# pcb01_control.net
KiCad netlist of a schematic drawn in EAGLE
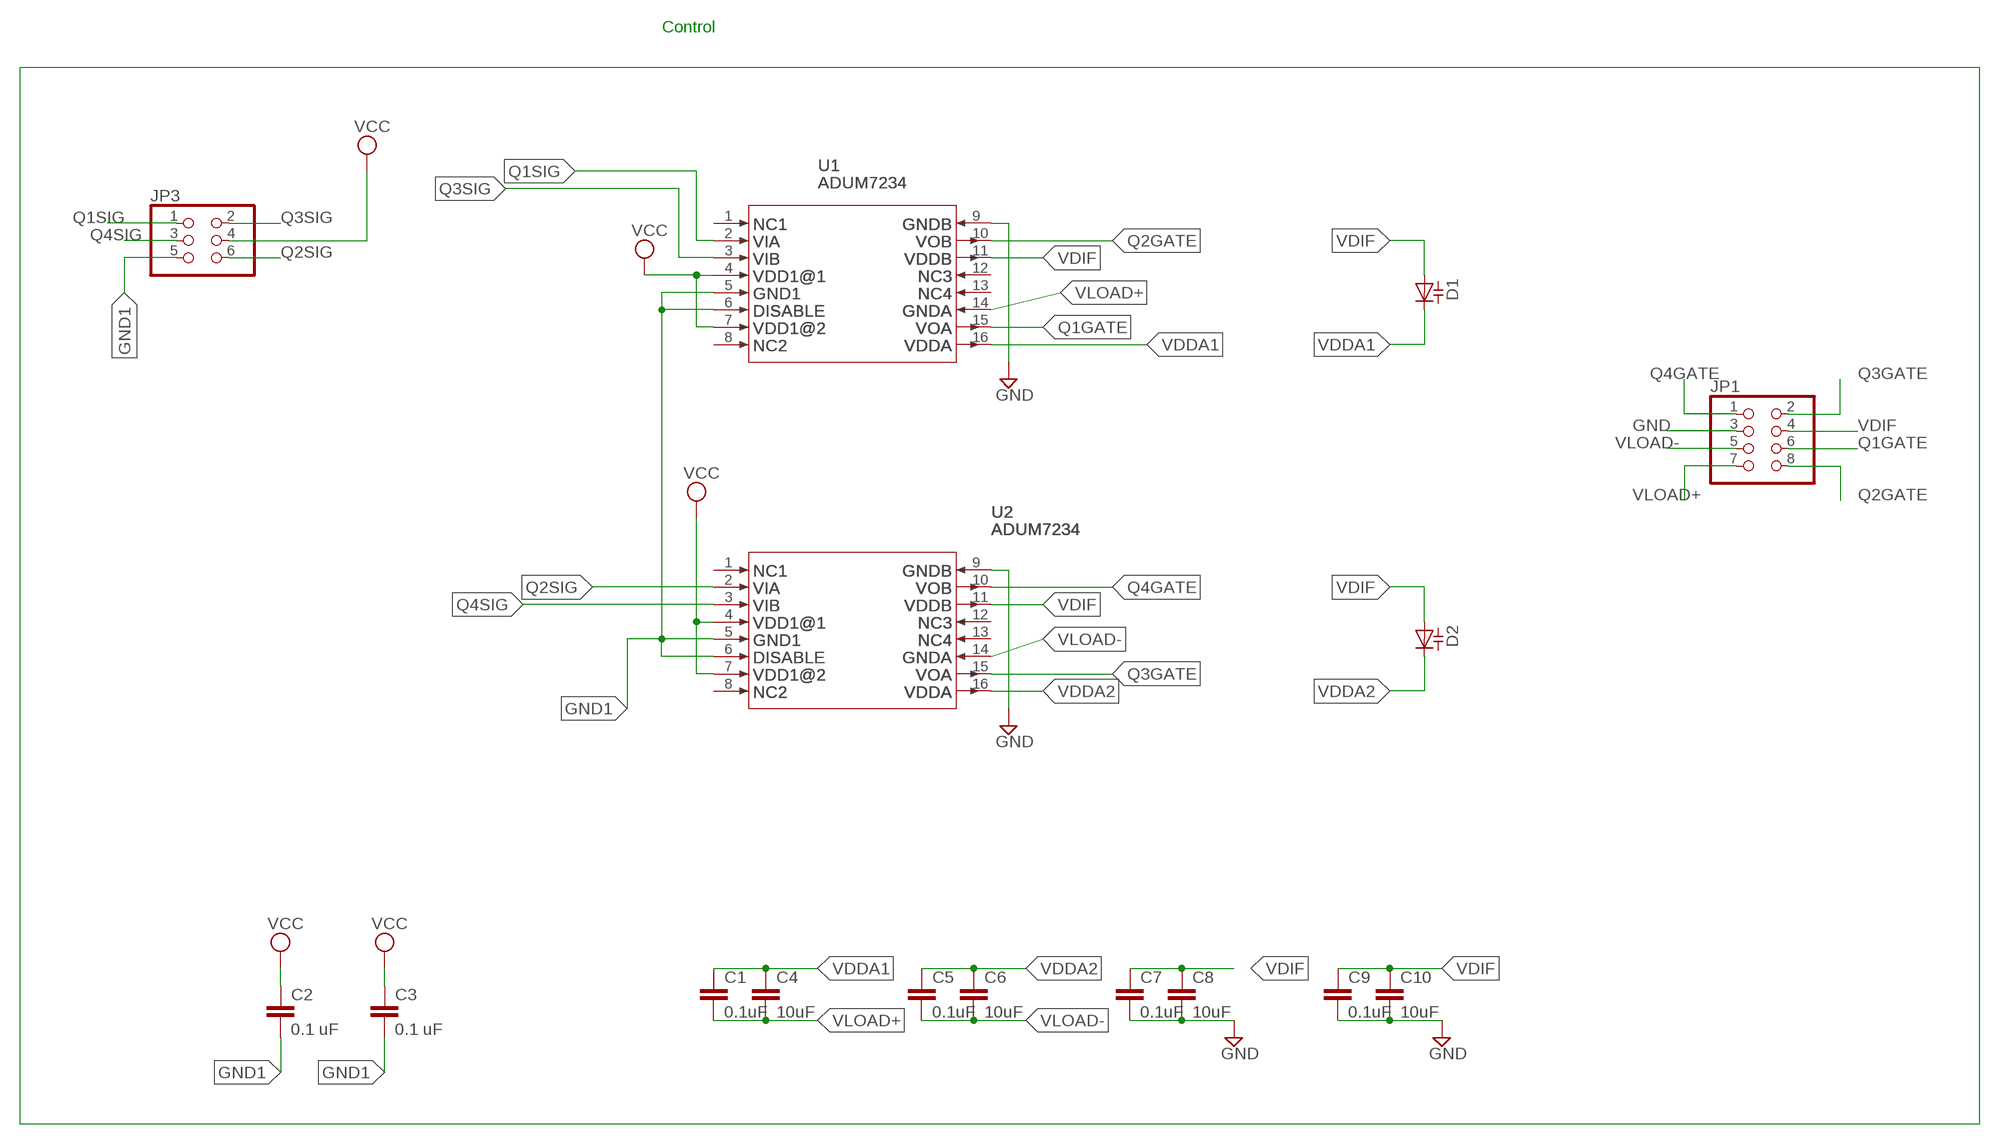
[diagram p0: schematic, sheet 1]

(export (version "E")
  (design (tool "Eeschema 10.0.6"))
  (components
    (comp (ref "C1")
      (value "0.1uF")
      (footprint "eagle-import:C0805")
      (libsource (lib "eagle-import") (part "resistor_C-EUC0805"))
    )
    (comp (ref "C2")
      (value "0.1 uF")
      (footprint "eagle-import:C0805")
      (libsource (lib "eagle-import") (part "C-EUC0805"))
    )
    (comp (ref "C3")
      (value "0.1 uF")
      (footprint "eagle-import:C0805")
      (libsource (lib "eagle-import") (part "C-EUC0805"))
    )
    (comp (ref "C4")
      (value "10uF")
      (footprint "eagle-import:C0805")
      (libsource (lib "eagle-import") (part "resistor_C-EUC0805"))
    )
    (comp (ref "C5")
      (value "0.1uF")
      (footprint "eagle-import:C0805")
      (libsource (lib "eagle-import") (part "resistor_C-EUC0805"))
    )
    (comp (ref "C6")
      (value "10uF")
      (footprint "eagle-import:C0805")
      (libsource (lib "eagle-import") (part "resistor_C-EUC0805"))
    )
    (comp (ref "C7")
      (value "0.1uF")
      (footprint "eagle-import:C0805")
      (libsource (lib "eagle-import") (part "resistor_C-EUC0805"))
    )
    (comp (ref "C8")
      (value "10uF")
      (footprint "eagle-import:C0805")
      (libsource (lib "eagle-import") (part "resistor_C-EUC0805"))
    )
    (comp (ref "C9")
      (value "0.1uF")
      (footprint "eagle-import:C0805")
      (libsource (lib "eagle-import") (part "resistor_C-EUC0805"))
    )
    (comp (ref "C10")
      (value "10uF")
      (footprint "eagle-import:C0805")
      (libsource (lib "eagle-import") (part "resistor_C-EUC0805"))
    )
    (comp (ref "D1")
      (value "DIODE_CAPACITANCE-SOD523")
      (footprint "eagle-import:SOD523")
      (libsource (lib "eagle-import") (part "DIODE_CAPACITANCE-SOD523"))
    )
    (comp (ref "D2")
      (value "DIODE_CAPACITANCE-SOD523")
      (footprint "eagle-import:SOD523")
      (libsource (lib "eagle-import") (part "DIODE_CAPACITANCE-SOD523"))
    )
    (comp (ref "JP1")
      (value "PINHD-2X4")
      (footprint "eagle-import:2X04")
      (libsource (lib "eagle-import") (part "PINHD-2X4"))
    )
    (comp (ref "JP3")
      (value "PINHD-2X3")
      (footprint "eagle-import:2X03")
      (libsource (lib "eagle-import") (part "PINHD-2X3"))
    )
    (comp (ref "U1")
      (value "ADUM7234")
      (footprint "eagle-import:16_SOIC")
      (libsource (lib "eagle-import") (part "ADUM7234"))
    )
    (comp (ref "U2")
      (value "ADUM7234")
      (footprint "eagle-import:16_SOIC")
      (libsource (lib "eagle-import") (part "ADUM7234"))
    )
  )
  (nets
    (net (code "1") (name "GND") (class "Default")
      (node (ref "C10") (pin "2") (pinfunction "2_2") (pintype "passive"))
      (node (ref "C7") (pin "2") (pinfunction "2_2") (pintype "passive"))
      (node (ref "C8") (pin "2") (pinfunction "2_2") (pintype "passive"))
      (node (ref "C9") (pin "2") (pinfunction "2_2") (pintype "passive"))
      (node (ref "JP1") (pin "3") (pinfunction "3_3") (pintype "passive"))
      (node (ref "U1") (pin "9") (pinfunction "1_9") (pintype "input"))
      (node (ref "U2") (pin "9") (pinfunction "1_9") (pintype "input"))
    )
    (net (code "2") (name "GND1") (class "Default")
      (node (ref "C2") (pin "2") (pinfunction "2_2") (pintype "passive"))
      (node (ref "C3") (pin "2") (pinfunction "2_2") (pintype "passive"))
      (node (ref "JP3") (pin "5") (pinfunction "5_5") (pintype "passive"))
      (node (ref "U1") (pin "5") (pinfunction "1_5") (pintype "input"))
      (node (ref "U1") (pin "6") (pinfunction "1_6") (pintype "input"))
      (node (ref "U2") (pin "5") (pinfunction "1_5") (pintype "input"))
      (node (ref "U2") (pin "6") (pinfunction "1_6") (pintype "input"))
    )
    (net (code "3") (name "Q1GATE") (class "Default")
      (node (ref "JP1") (pin "6") (pinfunction "6_6") (pintype "passive"))
      (node (ref "U1") (pin "15") (pinfunction "1_15") (pintype "output"))
    )
    (net (code "4") (name "Q1SIG") (class "Default")
      (node (ref "JP3") (pin "1") (pinfunction "1_1") (pintype "passive"))
      (node (ref "U1") (pin "2") (pinfunction "1_2") (pintype "input"))
    )
    (net (code "5") (name "Q2GATE") (class "Default")
      (node (ref "JP1") (pin "8") (pinfunction "8_8") (pintype "passive"))
      (node (ref "U1") (pin "10") (pinfunction "1_10") (pintype "output"))
    )
    (net (code "6") (name "Q2SIG") (class "Default")
      (node (ref "JP3") (pin "6") (pinfunction "6_6") (pintype "passive"))
      (node (ref "U2") (pin "2") (pinfunction "1_2") (pintype "input"))
    )
    (net (code "7") (name "Q3GATE") (class "Default")
      (node (ref "JP1") (pin "2") (pinfunction "2_2") (pintype "passive"))
      (node (ref "U2") (pin "15") (pinfunction "1_15") (pintype "output"))
    )
    (net (code "8") (name "Q3SIG") (class "Default")
      (node (ref "JP3") (pin "2") (pinfunction "2_2") (pintype "passive"))
      (node (ref "U1") (pin "3") (pinfunction "1_3") (pintype "input"))
    )
    (net (code "9") (name "Q4GATE") (class "Default")
      (node (ref "JP1") (pin "1") (pinfunction "1_1") (pintype "passive"))
      (node (ref "U2") (pin "10") (pinfunction "1_10") (pintype "output"))
    )
    (net (code "10") (name "Q4SIG") (class "Default")
      (node (ref "JP3") (pin "3") (pinfunction "3_3") (pintype "passive"))
      (node (ref "U2") (pin "3") (pinfunction "1_3") (pintype "input"))
    )
    (net (code "11") (name "VCC") (class "Default")
      (node (ref "C2") (pin "1") (pinfunction "1_1") (pintype "passive"))
      (node (ref "C3") (pin "1") (pinfunction "1_1") (pintype "passive"))
      (node (ref "JP3") (pin "4") (pinfunction "4_4") (pintype "passive"))
      (node (ref "U1") (pin "4") (pinfunction "1_4") (pintype "input"))
      (node (ref "U1") (pin "7") (pinfunction "1_7") (pintype "input"))
      (node (ref "U2") (pin "4") (pinfunction "1_4") (pintype "input"))
      (node (ref "U2") (pin "7") (pinfunction "1_7") (pintype "input"))
    )
    (net (code "12") (name "VDDA1") (class "Default")
      (node (ref "C1") (pin "1") (pinfunction "1_1") (pintype "passive"))
      (node (ref "C4") (pin "1") (pinfunction "1_1") (pintype "passive"))
      (node (ref "D1") (pin "C") (pinfunction "C_C") (pintype "passive"))
      (node (ref "U1") (pin "16") (pinfunction "1_16") (pintype "output"))
    )
    (net (code "13") (name "VDDA2") (class "Default")
      (node (ref "C5") (pin "1") (pinfunction "1_1") (pintype "passive"))
      (node (ref "C6") (pin "1") (pinfunction "1_1") (pintype "passive"))
      (node (ref "D2") (pin "C") (pinfunction "C_C") (pintype "passive"))
      (node (ref "U2") (pin "16") (pinfunction "1_16") (pintype "output"))
    )
    (net (code "14") (name "VDIF") (class "Default")
      (node (ref "C10") (pin "1") (pinfunction "1_1") (pintype "passive"))
      (node (ref "C7") (pin "1") (pinfunction "1_1") (pintype "passive"))
      (node (ref "C8") (pin "1") (pinfunction "1_1") (pintype "passive"))
      (node (ref "C9") (pin "1") (pinfunction "1_1") (pintype "passive"))
      (node (ref "D1") (pin "A") (pinfunction "A_A") (pintype "passive"))
      (node (ref "D2") (pin "A") (pinfunction "A_A") (pintype "passive"))
      (node (ref "JP1") (pin "4") (pinfunction "4_4") (pintype "passive"))
      (node (ref "U1") (pin "11") (pinfunction "1_11") (pintype "output"))
      (node (ref "U2") (pin "11") (pinfunction "1_11") (pintype "output"))
    )
    (net (code "15") (name "VLOAD+") (class "Default")
      (node (ref "C1") (pin "2") (pinfunction "2_2") (pintype "passive"))
      (node (ref "C4") (pin "2") (pinfunction "2_2") (pintype "passive"))
      (node (ref "JP1") (pin "7") (pinfunction "7_7") (pintype "passive"))
      (node (ref "U1") (pin "14") (pinfunction "1_14") (pintype "input"))
    )
    (net (code "16") (name "VLOAD-") (class "Default")
      (node (ref "C5") (pin "2") (pinfunction "2_2") (pintype "passive"))
      (node (ref "C6") (pin "2") (pinfunction "2_2") (pintype "passive"))
      (node (ref "JP1") (pin "5") (pinfunction "5_5") (pintype "passive"))
      (node (ref "U2") (pin "14") (pinfunction "1_14") (pintype "input"))
    )
    (net (code "17") (name "unconnected-(U1-Pad1)") (class "Default")
      (node (ref "U1") (pin "1") (pinfunction "1_1") (pintype "input"))
    )
    (net (code "18") (name "unconnected-(U1F-1-Pad8)") (class "Default")
      (node (ref "U1") (pin "8") (pinfunction "1_8") (pintype "input"))
    )
    (net (code "19") (name "unconnected-(U1G-1-Pad12)") (class "Default")
      (node (ref "U1") (pin "12") (pinfunction "1_12") (pintype "input"))
    )
    (net (code "20") (name "unconnected-(U1H-1-Pad13)") (class "Default")
      (node (ref "U1") (pin "13") (pinfunction "1_13") (pintype "input"))
    )
    (net (code "21") (name "unconnected-(U2-Pad1)") (class "Default")
      (node (ref "U2") (pin "1") (pinfunction "1_1") (pintype "input"))
    )
    (net (code "22") (name "unconnected-(U2F-1-Pad8)") (class "Default")
      (node (ref "U2") (pin "8") (pinfunction "1_8") (pintype "input"))
    )
    (net (code "23") (name "unconnected-(U2G-1-Pad12)") (class "Default")
      (node (ref "U2") (pin "12") (pinfunction "1_12") (pintype "input"))
    )
    (net (code "24") (name "unconnected-(U2H-1-Pad13)") (class "Default")
      (node (ref "U2") (pin "13") (pinfunction "1_13") (pintype "input"))
    )
  )
)
